# VUE_PIC32_v1_0_PIC32.net
KiCad netlist of a schematic drawn in Altium Designer
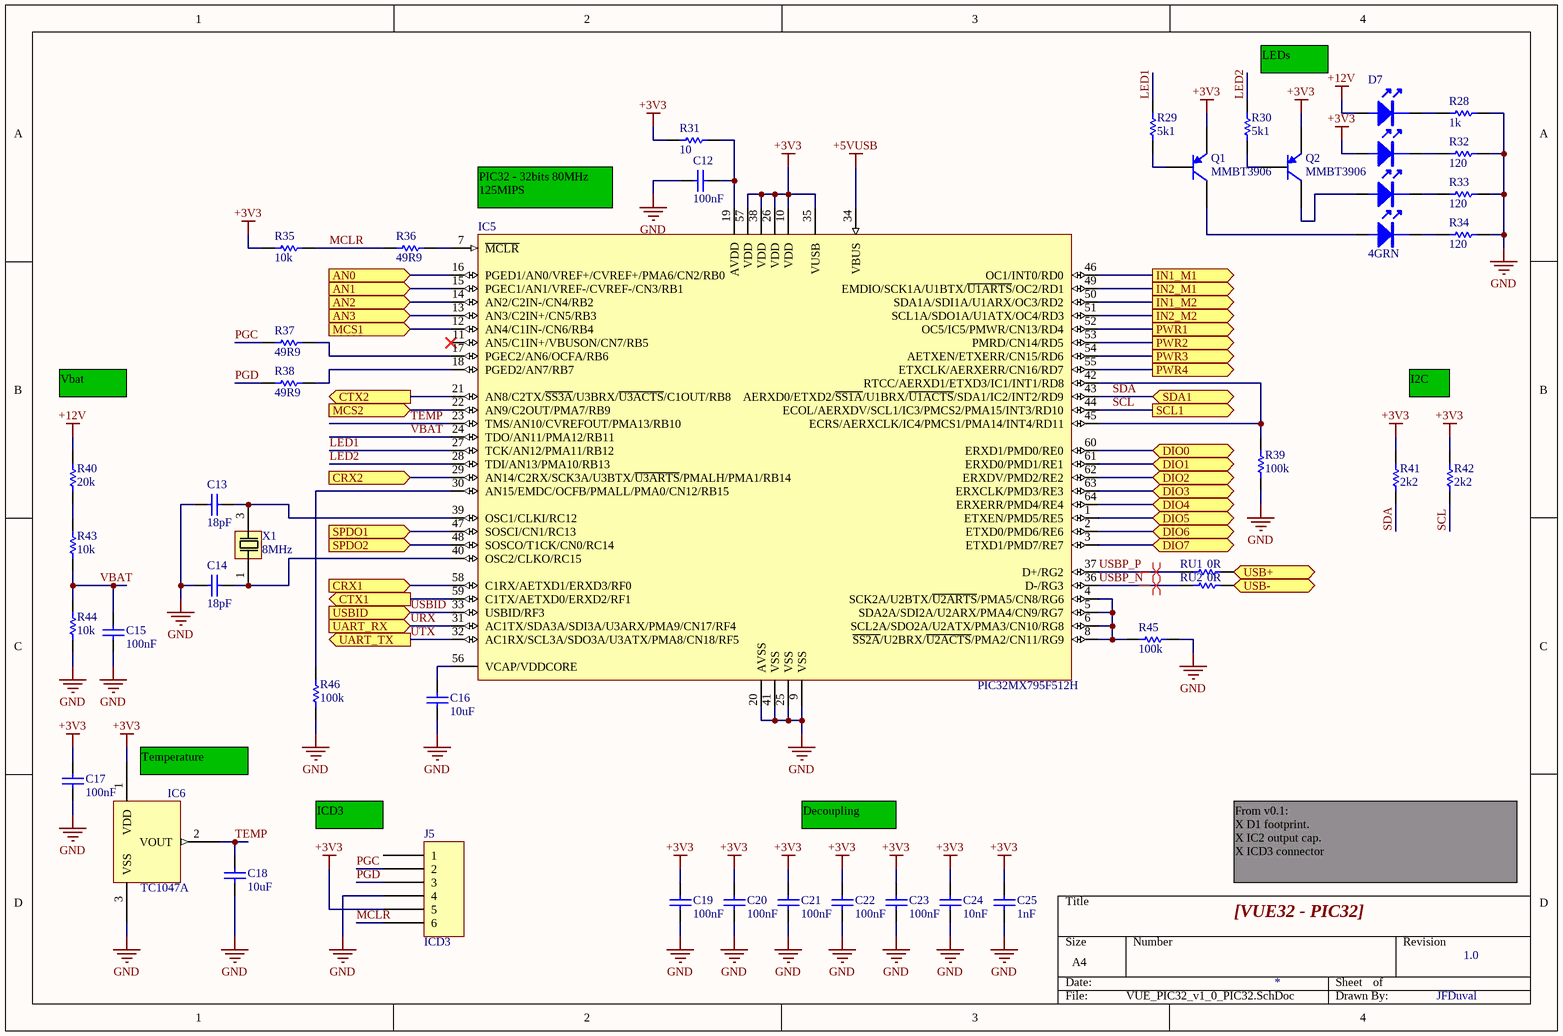
[diagram p0: VUE_PIC32_v1_0_PIC32.SchDoc]

(export (version "E")
  (design (tool "Eeschema 10.0.6"))
  (components
    (comp (ref "C12")
      (value "100nF")
      (footprint "0402C")
      (description "CAP CER 0.1UF 25V Y5V 0402")
      (fields (field (name "MFG") "TDK") (field (name "MFGPARTNUMBER") "C1005Y5V1E104Z"))
      (libsource (lib "JFD_Cap") (part "CAP_TDK_C_0402_100nF_25V"))
    )
    (comp (ref "C13")
      (value "18pF")
      (footprint "0402C")
      (description "CAP CER 18PF 50V 5% NP0 0402")
      (fields (field (name "MFG") "TDK") (field (name "MFGPARTNUMBER") "C1005C0G1H180J"))
      (libsource (lib "JFD_Cap") (part "CAP_TDK_C_0402_18pF_50V"))
    )
    (comp (ref "C14")
      (value "18pF")
      (footprint "0402C")
      (description "CAP CER 18PF 50V 5% NP0 0402")
      (fields (field (name "MFG") "TDK") (field (name "MFGPARTNUMBER") "C1005C0G1H180J"))
      (libsource (lib "JFD_Cap") (part "CAP_TDK_C_0402_18pF_50V"))
    )
    (comp (ref "C15")
      (value "100nF")
      (footprint "0402C")
      (description "CAP CER 0.1UF 25V Y5V 0402")
      (fields (field (name "MFG") "TDK") (field (name "MFGPARTNUMBER") "C1005Y5V1E104Z"))
      (libsource (lib "JFD_Cap") (part "CAP_TDK_C_0402_100nF_25V"))
    )
    (comp (ref "C16")
      (value "10uF")
      (footprint "0805C")
      (description "CAP CER 10UF 16V Y5V 0805")
      (fields (field (name "MFG") "Murata") (field (name "MFGPARTNUMBER") "GRM21BF51C106ZE15L"))
      (libsource (lib "JFD_Cap") (part "CAP_MURATA_C_0805_10uF_16V"))
    )
    (comp (ref "C17")
      (value "100nF")
      (footprint "0402C")
      (description "CAP CER 0.1UF 25V Y5V 0402")
      (fields (field (name "MFG") "TDK") (field (name "MFGPARTNUMBER") "C1005Y5V1E104Z"))
      (libsource (lib "JFD_Cap") (part "CAP_TDK_C_0402_100nF_25V"))
    )
    (comp (ref "C18")
      (value "10uF")
      (footprint "0805C")
      (description "CAP CER 10UF 16V Y5V 0805")
      (fields (field (name "MFG") "Murata") (field (name "MFGPARTNUMBER") "GRM21BF51C106ZE15L"))
      (libsource (lib "JFD_Cap") (part "CAP_MURATA_C_0805_10uF_16V"))
    )
    (comp (ref "C19")
      (value "100nF")
      (footprint "0402C")
      (description "CAP CER 0.1UF 25V Y5V 0402")
      (fields (field (name "MFG") "TDK") (field (name "MFGPARTNUMBER") "C1005Y5V1E104Z"))
      (libsource (lib "JFD_Cap") (part "CAP_TDK_C_0402_100nF_25V"))
    )
    (comp (ref "C20")
      (value "100nF")
      (footprint "0402C")
      (description "CAP CER 0.1UF 25V Y5V 0402")
      (fields (field (name "MFG") "TDK") (field (name "MFGPARTNUMBER") "C1005Y5V1E104Z"))
      (libsource (lib "JFD_Cap") (part "CAP_TDK_C_0402_100nF_25V"))
    )
    (comp (ref "C21")
      (value "100nF")
      (footprint "0402C")
      (description "CAP CER 0.1UF 25V Y5V 0402")
      (fields (field (name "MFG") "TDK") (field (name "MFGPARTNUMBER") "C1005Y5V1E104Z"))
      (libsource (lib "JFD_Cap") (part "CAP_TDK_C_0402_100nF_25V"))
    )
    (comp (ref "C22")
      (value "100nF")
      (footprint "0402C")
      (description "CAP CER 0.1UF 25V Y5V 0402")
      (fields (field (name "MFG") "TDK") (field (name "MFGPARTNUMBER") "C1005Y5V1E104Z"))
      (libsource (lib "JFD_Cap") (part "CAP_TDK_C_0402_100nF_25V"))
    )
    (comp (ref "C23")
      (value "100nF")
      (footprint "0402C")
      (description "CAP CER 0.1UF 25V Y5V 0402")
      (fields (field (name "MFG") "TDK") (field (name "MFGPARTNUMBER") "C1005Y5V1E104Z"))
      (libsource (lib "JFD_Cap") (part "CAP_TDK_C_0402_100nF_25V"))
    )
    (comp (ref "C24")
      (value "10nF")
      (footprint "0402C")
      (description "CAP CER 10000PF 25V 10% X7R 0402")
      (fields (field (name "MFG") "TDK") (field (name "MFGPARTNUMBER") "C1005X7R1E103K"))
      (libsource (lib "JFD_Cap") (part "CAP_TDK_C_0402_10nF_25V"))
    )
    (comp (ref "C25")
      (value "1nF")
      (footprint "0402C")
      (description "CAP CER 1000PF 25V 10% X7R 0402")
      (fields (field (name "MFG") "TDK") (field (name "MFGPARTNUMBER") "C1005X7R1E102K"))
      (libsource (lib "JFD_Cap") (part "CAP_TDK_C_0402_1nF_25V"))
    )
    (comp (ref "D7")
      (value "4GRN")
      (footprint "KINGBRIGHT_4HIGH_LED")
      (description "LED IND 2X3MM QUAD RA GRN DIFF")
      (fields (field (name "MFG") "Kingbright Corp") (field (name "MFGPARTNUMBER") "WP914CK/4GDT"))
      (libsource (lib "JFD_Semi") (part "LED_KINGBRIGHT_4HIGH_GREEN"))
    )
    (comp (ref "IC5")
      (value "PIC32MX795F512H")
      (footprint "TQFP-64")
      (description "IC MCU 32BIT 512KB FLASH 64TQFP")
      (fields
        (field (name "MFG") "Microchip Technology")
        (field (name "MFGPARTNUMBER") "PIC32MX795F512H-80I/PT")
      )
      (libsource (lib "JFD_IC") (part "IC_MCU_MICROCHIP_PIC32MX795F512H"))
    )
    (comp (ref "IC6")
      (value "TC1047A")
      (footprint "SOT23-3")
      (description "IC TEMP-VOLT CONV PREC SOT-23B")
      (fields (field (name "MFG") "Microchip Technology") (field (name "MFGPARTNUMBER") "TC1047AVNBTR"))
      (libsource (lib "JFD_IC") (part "IC_SENSOR_MICROCHIP_TEMP_TC1047A"))
    )
    (comp (ref "J5")
      (value "ICD3")
      (footprint "HEADER_FEMALE_DUAL_6POS_1_27MM")
      (description "CONN HEADER .050\" 6POS DL PCB AU")
      (fields
        (field (name "MFG") "Sullins Connector Solutions")
        (field (name "MFGPARTNUMBER") "LPPB032CFFN-RC")
      )
      (libsource (lib "JFD_Con") (part "CON_SULLINS_HEADER_F_3X2_6POS_1_27MM"))
    )
    (comp (ref "Q1")
      (value "MMBT3906")
      (footprint "SC-75/SOT-416")
      (description "TRANS PNP GP 40V 200MA SC75-3")
      (fields (field (name "MFG") "ON Semiconductor") (field (name "MFGPARTNUMBER") "MMBT3906TT1G"))
      (libsource (lib "JFD_Semi") (part "BJT_ONSEMI_PNP_MMBT3906_40V_200MA_SC75"))
    )
    (comp (ref "Q2")
      (value "MMBT3906")
      (footprint "SC-75/SOT-416")
      (description "TRANS PNP GP 40V 200MA SC75-3")
      (fields (field (name "MFG") "ON Semiconductor") (field (name "MFGPARTNUMBER") "MMBT3906TT1G"))
      (libsource (lib "JFD_Semi") (part "BJT_ONSEMI_PNP_MMBT3906_40V_200MA_SC75"))
    )
    (comp (ref "R28")
      (value "1k")
      (footprint "0402")
      (description "RES 1.00K OHM 1/16W 1% 0402 SMD")
      (fields (field (name "MFG") "Yageo") (field (name "MFGPARTNUMBER") "RC0402FR-071KL"))
      (libsource (lib "JFD_Res") (part "RES_YAGEO_0402_1K_1PCT"))
    )
    (comp (ref "R29")
      (value "5k1")
      (footprint "0402")
      (description "RES 5.10K OHM 1/16W 1% 0402 SMD")
      (fields (field (name "MFG") "Yageo") (field (name "MFGPARTNUMBER") "RC0402FR-075K1L"))
      (libsource (lib "JFD_Res") (part "RES_YAGEO_0402_5K1_1PCT"))
    )
    (comp (ref "R30")
      (value "5k1")
      (footprint "0402")
      (description "RES 5.10K OHM 1/16W 1% 0402 SMD")
      (fields (field (name "MFG") "Yageo") (field (name "MFGPARTNUMBER") "RC0402FR-075K1L"))
      (libsource (lib "JFD_Res") (part "RES_YAGEO_0402_5K1_1PCT"))
    )
    (comp (ref "R31")
      (value "10")
      (footprint "0402")
      (description "RES 10.0 OHM 1/16W 1% 0402 SMD")
      (fields (field (name "MFG") "Yageo") (field (name "MFGPARTNUMBER") "RC0402FR-0710RL"))
      (libsource (lib "JFD_Res") (part "RES_YAGEO_0402_10_1PCT"))
    )
    (comp (ref "R32")
      (value "120")
      (footprint "0402")
      (description "RES 120 OHM 1/16W 1% 0402 SMD")
      (fields (field (name "MFG") "Yageo") (field (name "MFGPARTNUMBER") "RC0402FR-07120RL"))
      (libsource (lib "JFD_Res") (part "RES_YAGEO_0402_120_1PCT"))
    )
    (comp (ref "R33")
      (value "120")
      (footprint "0402")
      (description "RES 120 OHM 1/16W 1% 0402 SMD")
      (fields (field (name "MFG") "Yageo") (field (name "MFGPARTNUMBER") "RC0402FR-07120RL"))
      (libsource (lib "JFD_Res") (part "RES_YAGEO_0402_120_1PCT"))
    )
    (comp (ref "R34")
      (value "120")
      (footprint "0402")
      (description "RES 120 OHM 1/16W 1% 0402 SMD")
      (fields (field (name "MFG") "Yageo") (field (name "MFGPARTNUMBER") "RC0402FR-07120RL"))
      (libsource (lib "JFD_Res") (part "RES_YAGEO_0402_120_1PCT"))
    )
    (comp (ref "R35")
      (value "10k")
      (footprint "0402")
      (description "RES 10.0K OHM 1/16W 1% 0402 SMD")
      (fields (field (name "MFG") "Yageo") (field (name "MFGPARTNUMBER") "RC0402FR-0710KL"))
      (libsource (lib "JFD_Res") (part "RES_YAGEO_0402_10K_1PCT"))
    )
    (comp (ref "R36")
      (value "49R9")
      (footprint "0402")
      (description "RES 49.9 OHM 1/16W 1% 0402 SMD")
      (fields (field (name "MFG") "Yageo") (field (name "MFGPARTNUMBER") "RC0402FR-0749R9L"))
      (libsource (lib "JFD_Res") (part "RES_YAGEO_0402_49R9_1PCT"))
    )
    (comp (ref "R37")
      (value "49R9")
      (footprint "0402")
      (description "RES 49.9 OHM 1/16W 1% 0402 SMD")
      (fields (field (name "MFG") "Yageo") (field (name "MFGPARTNUMBER") "RC0402FR-0749R9L"))
      (libsource (lib "JFD_Res") (part "RES_YAGEO_0402_49R9_1PCT"))
    )
    (comp (ref "R38")
      (value "49R9")
      (footprint "0402")
      (description "RES 49.9 OHM 1/16W 1% 0402 SMD")
      (fields (field (name "MFG") "Yageo") (field (name "MFGPARTNUMBER") "RC0402FR-0749R9L"))
      (libsource (lib "JFD_Res") (part "RES_YAGEO_0402_49R9_1PCT"))
    )
    (comp (ref "R39")
      (value "100k")
      (footprint "0402")
      (description "RES 100K OHM 1/16W 1% 0402 SMD")
      (fields (field (name "MFG") "Yageo") (field (name "MFGPARTNUMBER") "RC0402FR-07100KL"))
      (libsource (lib "JFD_Res") (part "RES_YAGEO_0402_100K_1PCT"))
    )
    (comp (ref "R40")
      (value "20k")
      (footprint "0402")
      (description "RES 20.0K OHM 1/16W 1% 0402 SMD")
      (fields (field (name "MFG") "Yageo") (field (name "MFGPARTNUMBER") "RC0402FR-0720KL"))
      (libsource (lib "JFD_Res") (part "RES_YAGEO_0402_20K_1PCT"))
    )
    (comp (ref "R41")
      (value "2k2")
      (footprint "0402")
      (description "RES 2.20K OHM 1/16W 1% 0402 SMD")
      (fields (field (name "MFG") "Yageo") (field (name "MFGPARTNUMBER") "RC0402FR-072K2L"))
      (libsource (lib "JFD_Res") (part "RES_YAGEO_0402_2K2_1PCT"))
    )
    (comp (ref "R42")
      (value "2k2")
      (footprint "0402")
      (description "RES 2.20K OHM 1/16W 1% 0402 SMD")
      (fields (field (name "MFG") "Yageo") (field (name "MFGPARTNUMBER") "RC0402FR-072K2L"))
      (libsource (lib "JFD_Res") (part "RES_YAGEO_0402_2K2_1PCT"))
    )
    (comp (ref "R43")
      (value "10k")
      (footprint "0402")
      (description "RES 10.0K OHM 1/16W 1% 0402 SMD")
      (fields (field (name "MFG") "Yageo") (field (name "MFGPARTNUMBER") "RC0402FR-0710KL"))
      (libsource (lib "JFD_Res") (part "RES_YAGEO_0402_10K_1PCT"))
    )
    (comp (ref "R44")
      (value "10k")
      (footprint "0402")
      (description "RES 10.0K OHM 1/16W 1% 0402 SMD")
      (fields (field (name "MFG") "Yageo") (field (name "MFGPARTNUMBER") "RC0402FR-0710KL"))
      (libsource (lib "JFD_Res") (part "RES_YAGEO_0402_10K_1PCT"))
    )
    (comp (ref "R45")
      (value "100k")
      (footprint "0402")
      (description "RES 100K OHM 1/16W 1% 0402 SMD")
      (fields (field (name "MFG") "Yageo") (field (name "MFGPARTNUMBER") "RC0402FR-07100KL"))
      (libsource (lib "JFD_Res") (part "RES_YAGEO_0402_100K_1PCT"))
    )
    (comp (ref "R46")
      (value "100k")
      (footprint "0402")
      (description "RES 100K OHM 1/16W 1% 0402 SMD")
      (fields (field (name "MFG") "Yageo") (field (name "MFGPARTNUMBER") "RC0402FR-07100KL"))
      (libsource (lib "JFD_Res") (part "RES_YAGEO_0402_100K_1PCT"))
    )
    (comp (ref "RU1")
      (value "0R")
      (footprint "0402")
      (description "RES 0.0 OHM 1/16W 0402 SMD")
      (fields (field (name "MFG") "Yageo") (field (name "MFGPARTNUMBER") "RC0402JR-070RL"))
      (libsource (lib "JFD_Res") (part "RES_YAGEO_0402_0R_1PCT"))
    )
    (comp (ref "RU2")
      (value "0R")
      (footprint "0402")
      (description "RES 0.0 OHM 1/16W 0402 SMD")
      (fields (field (name "MFG") "Yageo") (field (name "MFGPARTNUMBER") "RC0402JR-070RL"))
      (libsource (lib "JFD_Res") (part "RES_YAGEO_0402_0R_1PCT"))
    )
    (comp (ref "X1")
      (value "8MHz")
      (footprint "ABBM2")
      (description "CRYSTAL 8.000 MHZ 18PF SMD")
      (fields (field (name "MFG") "Abracon Corporation") (field (name "MFGPARTNUMBER") "ABMM2-8.000MHZ-E2-T"))
      (libsource (lib "JFD_Misc") (part "CRYSTAL_ABRACON_8MHZ_OSC"))
    )
  )
  (nets
    (net (code "1") (name "+3V3") (class "Default")
      (node (ref "C17") (pin "1") (pinfunction "1_1") (pintype "passive"))
      (node (ref "C19") (pin "1") (pinfunction "1_1") (pintype "passive"))
      (node (ref "C20") (pin "1") (pinfunction "1_1") (pintype "passive"))
      (node (ref "C21") (pin "1") (pinfunction "1_1") (pintype "passive"))
      (node (ref "C22") (pin "1") (pinfunction "1_1") (pintype "passive"))
      (node (ref "C23") (pin "1") (pinfunction "1_1") (pintype "passive"))
      (node (ref "C24") (pin "2") (pinfunction "2_2") (pintype "passive"))
      (node (ref "C25") (pin "2") (pinfunction "2_2") (pintype "passive"))
      (node (ref "D7") (pin "A3") (pinfunction "A3_A3") (pintype "passive"))
      (node (ref "IC5") (pin "10") (pinfunction "VDD_10") (pintype "power_in"))
      (node (ref "IC5") (pin "26") (pinfunction "VDD_26") (pintype "power_in"))
      (node (ref "IC5") (pin "35") (pinfunction "VUSB_35") (pintype "power_in"))
      (node (ref "IC5") (pin "38") (pinfunction "VDD_38") (pintype "power_in"))
      (node (ref "IC5") (pin "57") (pinfunction "VDD_57") (pintype "power_in"))
      (node (ref "IC6") (pin "1") (pinfunction "VDD_1") (pintype "power_in"))
      (node (ref "J5") (pin "5") (pinfunction "5_5") (pintype "passive"))
      (node (ref "Q1") (pin "2") (pinfunction "E_2") (pintype "passive"))
      (node (ref "Q2") (pin "2") (pinfunction "E_2") (pintype "passive"))
      (node (ref "R31") (pin "2") (pinfunction "2_2") (pintype "passive"))
      (node (ref "R35") (pin "1") (pinfunction "1_1") (pintype "passive"))
      (node (ref "R41") (pin "2") (pinfunction "2_2") (pintype "passive"))
      (node (ref "R42") (pin "2") (pinfunction "2_2") (pintype "passive"))
    )
    (net (code "2") (name "+5VUSB") (class "Default")
      (node (ref "IC5") (pin "34") (pinfunction "VBUS_34") (pintype "input"))
    )
    (net (code "3") (name "+12V") (class "Default")
      (node (ref "D7") (pin "A4") (pinfunction "A4_A4") (pintype "passive"))
      (node (ref "R40") (pin "2") (pinfunction "2_2") (pintype "passive"))
    )
    (net (code "4") (name "/AN0") (class "Default")
      (node (ref "IC5") (pin "16") (pinfunction "PGED1/AN0/VREF+/CVREF+/PMA6/CN2/RB0_16") (pintype "bidirectional"))
    )
    (net (code "5") (name "/AN1") (class "Default")
      (node (ref "IC5") (pin "15") (pinfunction "PGEC1/AN1/VREF-/CVREF-/CN3/RB1_15") (pintype "bidirectional"))
    )
    (net (code "6") (name "/AN2") (class "Default")
      (node (ref "IC5") (pin "14") (pinfunction "AN2/C2IN-/CN4/RB2_14") (pintype "bidirectional"))
    )
    (net (code "7") (name "/AN3") (class "Default")
      (node (ref "IC5") (pin "13") (pinfunction "AN3/C2IN+/CN5/RB3_13") (pintype "bidirectional"))
    )
    (net (code "8") (name "/CRX1") (class "Default")
      (node (ref "IC5") (pin "58") (pinfunction "C1RX/AETXD1/ERXD3/RF0_58") (pintype "bidirectional"))
    )
    (net (code "9") (name "/CRX2") (class "Default")
      (node (ref "IC5") (pin "29") (pinfunction "AN14/C2RX/SCK3A/U3BTX/~{U3ARTS}/PMALH/PMA1/RB14_29") (pintype "bidirectional"))
    )
    (net (code "10") (name "/CTX1") (class "Default")
      (node (ref "IC5") (pin "59") (pinfunction "C1TX/AETXD0/ERXD2/RF1_59") (pintype "bidirectional"))
    )
    (net (code "11") (name "/CTX2") (class "Default")
      (node (ref "IC5") (pin "21") (pinfunction "AN8/C2TX/~{SS3A}/U3BRX/~{U3ACTS}/C1OUT/RB8_21") (pintype "bidirectional"))
    )
    (net (code "12") (name "/DIO0") (class "Default")
      (node (ref "IC5") (pin "60") (pinfunction "ERXD1/PMD0/RE0_60") (pintype "bidirectional"))
    )
    (net (code "13") (name "/DIO1") (class "Default")
      (node (ref "IC5") (pin "61") (pinfunction "ERXD0/PMD1/RE1_61") (pintype "bidirectional"))
    )
    (net (code "14") (name "/DIO2") (class "Default")
      (node (ref "IC5") (pin "62") (pinfunction "ERXDV/PMD2/RE2_62") (pintype "bidirectional"))
    )
    (net (code "15") (name "/DIO3") (class "Default")
      (node (ref "IC5") (pin "63") (pinfunction "ERXCLK/PMD3/RE3_63") (pintype "bidirectional"))
    )
    (net (code "16") (name "/DIO4") (class "Default")
      (node (ref "IC5") (pin "64") (pinfunction "ERXERR/PMD4/RE4_64") (pintype "bidirectional"))
    )
    (net (code "17") (name "/DIO5") (class "Default")
      (node (ref "IC5") (pin "1") (pinfunction "ETXEN/PMD5/RE5_1") (pintype "bidirectional"))
    )
    (net (code "18") (name "/DIO6") (class "Default")
      (node (ref "IC5") (pin "2") (pinfunction "ETXD0/PMD6/RE6_2") (pintype "bidirectional"))
    )
    (net (code "19") (name "/DIO7") (class "Default")
      (node (ref "IC5") (pin "3") (pinfunction "ETXD1/PMD7/RE7_3") (pintype "bidirectional"))
    )
    (net (code "20") (name "/IN1_M1") (class "Default")
      (node (ref "IC5") (pin "46") (pinfunction "OC1/INT0/RD0_46") (pintype "bidirectional"))
    )
    (net (code "21") (name "/IN1_M2") (class "Default")
      (node (ref "IC5") (pin "50") (pinfunction "SDA1A/SDI1A/U1ARX/OC3/RD2_50") (pintype "bidirectional"))
    )
    (net (code "22") (name "/IN2_M1") (class "Default")
      (node (ref "IC5") (pin "49") (pinfunction "EMDIO/SCK1A/U1BTX/~{U1ARTS}/OC2/RD1_49") (pintype "bidirectional"))
    )
    (net (code "23") (name "/IN2_M2") (class "Default")
      (node (ref "IC5") (pin "51") (pinfunction "SCL1A/SDO1A/U1ATX/OC4/RD3_51") (pintype "bidirectional"))
    )
    (net (code "24") (name "/LED1") (class "Default")
      (node (ref "IC5") (pin "27") (pinfunction "TCK/AN12/PMA11/RB12_27") (pintype "bidirectional"))
      (node (ref "R29") (pin "2") (pinfunction "2_2") (pintype "passive"))
    )
    (net (code "25") (name "/LED2") (class "Default")
      (node (ref "IC5") (pin "28") (pinfunction "TDI/AN13/PMA10/RB13_28") (pintype "bidirectional"))
      (node (ref "R30") (pin "2") (pinfunction "2_2") (pintype "passive"))
    )
    (net (code "26") (name "/MCLR") (class "Default")
      (node (ref "J5") (pin "6") (pinfunction "6_6") (pintype "passive"))
      (node (ref "R35") (pin "2") (pinfunction "2_2") (pintype "passive"))
      (node (ref "R36") (pin "1") (pinfunction "1_1") (pintype "passive"))
    )
    (net (code "27") (name "/MCS1") (class "Default")
      (node (ref "IC5") (pin "12") (pinfunction "AN4/C1IN-/CN6/RB4_12") (pintype "bidirectional"))
    )
    (net (code "28") (name "/MCS2") (class "Default")
      (node (ref "IC5") (pin "22") (pinfunction "AN9/C2OUT/PMA7/RB9_22") (pintype "bidirectional"))
    )
    (net (code "29") (name "/PGC") (class "Default")
      (node (ref "J5") (pin "2") (pinfunction "2_2") (pintype "passive"))
      (node (ref "R37") (pin "1") (pinfunction "1_1") (pintype "passive"))
    )
    (net (code "30") (name "/PGD") (class "Default")
      (node (ref "J5") (pin "3") (pinfunction "3_3") (pintype "passive"))
      (node (ref "R38") (pin "1") (pinfunction "1_1") (pintype "passive"))
    )
    (net (code "31") (name "/PWR1") (class "Default")
      (node (ref "IC5") (pin "52") (pinfunction "OC5/IC5/PMWR/CN13/RD4_52") (pintype "bidirectional"))
    )
    (net (code "32") (name "/PWR2") (class "Default")
      (node (ref "IC5") (pin "53") (pinfunction "PMRD/CN14/RD5_53") (pintype "bidirectional"))
    )
    (net (code "33") (name "/PWR3") (class "Default")
      (node (ref "IC5") (pin "54") (pinfunction "AETXEN/ETXERR/CN15/RD6_54") (pintype "bidirectional"))
    )
    (net (code "34") (name "/PWR4") (class "Default")
      (node (ref "IC5") (pin "55") (pinfunction "ETXCLK/AERXERR/CN16/RD7_55") (pintype "bidirectional"))
    )
    (net (code "35") (name "/SCL") (class "Default")
      (node (ref "IC5") (pin "44") (pinfunction "ECOL/AERXDV/SCL1/IC3/PMCS2/PMA15/INT3/RD10_44") (pintype "bidirectional"))
      (node (ref "R42") (pin "1") (pinfunction "1_1") (pintype "passive"))
    )
    (net (code "36") (name "/SDA") (class "Default")
      (node (ref "IC5") (pin "43") (pinfunction "AERXD0/ETXD2/~{SS1A}/U1BRX/~{U1ACTS}/SDA1/IC2/INT2/RD9_43") (pintype "bidirectional"))
      (node (ref "R41") (pin "1") (pinfunction "1_1") (pintype "passive"))
    )
    (net (code "37") (name "/SPDO1") (class "Default")
      (node (ref "IC5") (pin "47") (pinfunction "SOSCI/CN1/RC13_47") (pintype "bidirectional"))
    )
    (net (code "38") (name "/SPDO2") (class "Default")
      (node (ref "IC5") (pin "48") (pinfunction "SOSCO/T1CK/CN0/RC14_48") (pintype "bidirectional"))
    )
    (net (code "39") (name "/TEMP") (class "Default")
      (node (ref "C18") (pin "2") (pinfunction "2_2") (pintype "passive"))
      (node (ref "IC5") (pin "23") (pinfunction "TMS/AN10/CVREFOUT/PMA13/RB10_23") (pintype "bidirectional"))
      (node (ref "IC6") (pin "2") (pinfunction "VOUT_2") (pintype "output"))
    )
    (net (code "40") (name "/URX") (class "Default")
      (node (ref "IC5") (pin "31") (pinfunction "AC1TX/SDA3A/SDI3A/U3ARX/PMA9/CN17/RF4_31") (pintype "bidirectional"))
    )
    (net (code "41") (name "/USB+") (class "Default")
      (node (ref "RU1") (pin "2") (pinfunction "2_2") (pintype "passive"))
    )
    (net (code "42") (name "/USB-") (class "Default")
      (node (ref "RU2") (pin "2") (pinfunction "2_2") (pintype "passive"))
    )
    (net (code "43") (name "/USBID") (class "Default")
      (node (ref "IC5") (pin "33") (pinfunction "USBID/RF3_33") (pintype "bidirectional"))
    )
    (net (code "44") (name "/USBP_N") (class "Default")
      (node (ref "IC5") (pin "36") (pinfunction "D-/RG3_36") (pintype "bidirectional"))
      (node (ref "RU2") (pin "1") (pinfunction "1_1") (pintype "passive"))
    )
    (net (code "45") (name "/USBP_P") (class "Default")
      (node (ref "IC5") (pin "37") (pinfunction "D+/RG2_37") (pintype "bidirectional"))
      (node (ref "RU1") (pin "1") (pinfunction "1_1") (pintype "passive"))
    )
    (net (code "46") (name "/UTX") (class "Default")
      (node (ref "IC5") (pin "32") (pinfunction "AC1RX/SCL3A/SDO3A/U3ATX/PMA8/CN18/RF5_32") (pintype "bidirectional"))
    )
    (net (code "47") (name "/VBAT") (class "Default")
      (node (ref "C15") (pin "1") (pinfunction "1_1") (pintype "passive"))
      (node (ref "IC5") (pin "24") (pinfunction "TDO/AN11/PMA12/RB11_24") (pintype "bidirectional"))
      (node (ref "R43") (pin "1") (pinfunction "1_1") (pintype "passive"))
      (node (ref "R44") (pin "2") (pinfunction "2_2") (pintype "passive"))
    )
    (net (code "48") (name "GND") (class "Default")
      (node (ref "C12") (pin "2") (pinfunction "2_2") (pintype "passive"))
      (node (ref "C13") (pin "2") (pinfunction "2_2") (pintype "passive"))
      (node (ref "C14") (pin "2") (pinfunction "2_2") (pintype "passive"))
      (node (ref "C15") (pin "2") (pinfunction "2_2") (pintype "passive"))
      (node (ref "C16") (pin "1") (pinfunction "1_1") (pintype "passive"))
      (node (ref "C17") (pin "2") (pinfunction "2_2") (pintype "passive"))
      (node (ref "C18") (pin "1") (pinfunction "1_1") (pintype "passive"))
      (node (ref "C19") (pin "2") (pinfunction "2_2") (pintype "passive"))
      (node (ref "C20") (pin "2") (pinfunction "2_2") (pintype "passive"))
      (node (ref "C21") (pin "2") (pinfunction "2_2") (pintype "passive"))
      (node (ref "C22") (pin "2") (pinfunction "2_2") (pintype "passive"))
      (node (ref "C23") (pin "2") (pinfunction "2_2") (pintype "passive"))
      (node (ref "C24") (pin "1") (pinfunction "1_1") (pintype "passive"))
      (node (ref "C25") (pin "1") (pinfunction "1_1") (pintype "passive"))
      (node (ref "IC5") (pin "20") (pinfunction "AVSS_20") (pintype "power_in"))
      (node (ref "IC5") (pin "25") (pinfunction "VSS_25") (pintype "power_in"))
      (node (ref "IC5") (pin "41") (pinfunction "VSS_41") (pintype "power_in"))
      (node (ref "IC5") (pin "9") (pinfunction "VSS_9") (pintype "power_in"))
      (node (ref "IC6") (pin "3") (pinfunction "VSS_3") (pintype "power_in"))
      (node (ref "J5") (pin "4") (pinfunction "4_4") (pintype "passive"))
      (node (ref "R28") (pin "1") (pinfunction "1_1") (pintype "passive"))
      (node (ref "R32") (pin "2") (pinfunction "2_2") (pintype "passive"))
      (node (ref "R33") (pin "2") (pinfunction "2_2") (pintype "passive"))
      (node (ref "R34") (pin "2") (pinfunction "2_2") (pintype "passive"))
      (node (ref "R39") (pin "1") (pinfunction "1_1") (pintype "passive"))
      (node (ref "R44") (pin "1") (pinfunction "1_1") (pintype "passive"))
      (node (ref "R45") (pin "2") (pinfunction "2_2") (pintype "passive"))
      (node (ref "R46") (pin "1") (pinfunction "1_1") (pintype "passive"))
    )
    (net (code "49") (name "Net-(D7-PadC1)") (class "Default")
      (node (ref "D7") (pin "C1") (pinfunction "C1_C1") (pintype "passive"))
      (node (ref "R34") (pin "1") (pinfunction "1_1") (pintype "passive"))
    )
    (net (code "50") (name "Net-(D7-PadC2)") (class "Default")
      (node (ref "D7") (pin "C2") (pinfunction "C2_C2") (pintype "passive"))
      (node (ref "R33") (pin "1") (pinfunction "1_1") (pintype "passive"))
    )
    (net (code "51") (name "Net-(D7-PadC3)") (class "Default")
      (node (ref "D7") (pin "C3") (pinfunction "C3_C3") (pintype "passive"))
      (node (ref "R32") (pin "1") (pinfunction "1_1") (pintype "passive"))
    )
    (net (code "52") (name "Net-(D7-PadC4)") (class "Default")
      (node (ref "D7") (pin "C4") (pinfunction "C4_C4") (pintype "passive"))
      (node (ref "R28") (pin "2") (pinfunction "2_2") (pintype "passive"))
    )
    (net (code "53") (name "Net-(IC5-AN15{slash}EMDC{slash}OCFB{slash}PMALL{slash}PMA0{slash}CN12{slash}RB15)") (class "Default")
      (node (ref "IC5") (pin "30") (pinfunction "AN15/EMDC/OCFB/PMALL/PMA0/CN12/RB15_30") (pintype "bidirectional"))
      (node (ref "R46") (pin "2") (pinfunction "2_2") (pintype "passive"))
    )
    (net (code "54") (name "Net-(IC5-AVDD)") (class "Default")
      (node (ref "C12") (pin "1") (pinfunction "1_1") (pintype "passive"))
      (node (ref "IC5") (pin "19") (pinfunction "AVDD_19") (pintype "power_in"))
      (node (ref "R31") (pin "1") (pinfunction "1_1") (pintype "passive"))
    )
    (net (code "55") (name "Net-(IC5-ECRS{slash}AERXCLK{slash}IC4{slash}PMCS1{slash}PMA14{slash}INT4{slash}RD11)") (class "Default")
      (node (ref "IC5") (pin "42") (pinfunction "RTCC/AERXD1/ETXD3/IC1/INT1/RD8_42") (pintype "bidirectional"))
      (node (ref "IC5") (pin "45") (pinfunction "ECRS/AERXCLK/IC4/PMCS1/PMA14/INT4/RD11_45") (pintype "bidirectional"))
      (node (ref "R39") (pin "2") (pinfunction "2_2") (pintype "passive"))
    )
    (net (code "56") (name "Net-(IC5-OSC1{slash}CLKI{slash}RC12)") (class "Default")
      (node (ref "C13") (pin "1") (pinfunction "1_1") (pintype "passive"))
      (node (ref "IC5") (pin "39") (pinfunction "OSC1/CLKI/RC12_39") (pintype "bidirectional"))
      (node (ref "X1") (pin "3") (pinfunction "B_3") (pintype "passive"))
    )
    (net (code "57") (name "Net-(IC5-OSC2{slash}CLKO{slash}RC15)") (class "Default")
      (node (ref "C14") (pin "1") (pinfunction "1_1") (pintype "passive"))
      (node (ref "IC5") (pin "40") (pinfunction "OSC2/CLKO/RC15_40") (pintype "bidirectional"))
      (node (ref "X1") (pin "1") (pinfunction "A_1") (pintype "passive"))
    )
    (net (code "58") (name "Net-(IC5-PGEC2{slash}AN6{slash}OCFA{slash}RB6)") (class "Default")
      (node (ref "IC5") (pin "17") (pinfunction "PGEC2/AN6/OCFA/RB6_17") (pintype "bidirectional"))
      (node (ref "R37") (pin "2") (pinfunction "2_2") (pintype "passive"))
    )
    (net (code "59") (name "Net-(IC5-PGED2{slash}AN7{slash}RB7)") (class "Default")
      (node (ref "IC5") (pin "18") (pinfunction "PGED2/AN7/RB7_18") (pintype "bidirectional"))
      (node (ref "R38") (pin "2") (pinfunction "2_2") (pintype "passive"))
    )
    (net (code "60") (name "Net-(IC5-SCK2A{slash}U2BTX{slash}~{U2ARTS}{slash}PMA5{slash}CN8{slash}RG6)") (class "Default")
      (node (ref "IC5") (pin "4") (pinfunction "SCK2A/U2BTX/~{U2ARTS}/PMA5/CN8/RG6_4") (pintype "bidirectional"))
      (node (ref "IC5") (pin "5") (pinfunction "SDA2A/SDI2A/U2ARX/PMA4/CN9/RG7_5") (pintype "bidirectional"))
      (node (ref "IC5") (pin "6") (pinfunction "SCL2A/SDO2A/U2ATX/PMA3/CN10/RG8_6") (pintype "bidirectional"))
      (node (ref "IC5") (pin "8") (pinfunction "~{SS2A}/U2BRX/~{U2ACTS}/PMA2/CN11/RG9_8") (pintype "bidirectional"))
      (node (ref "R45") (pin "1") (pinfunction "1_1") (pintype "passive"))
    )
    (net (code "61") (name "Net-(IC5-VCAP{slash}VDDCORE)") (class "Default")
      (node (ref "C16") (pin "2") (pinfunction "2_2") (pintype "passive"))
      (node (ref "IC5") (pin "56") (pinfunction "VCAP/VDDCORE_56") (pintype "power_in"))
    )
    (net (code "62") (name "Net-(IC5-~{MCLR})") (class "Default")
      (node (ref "IC5") (pin "7") (pinfunction "~{MCLR}_7") (pintype "input"))
      (node (ref "R36") (pin "2") (pinfunction "2_2") (pintype "passive"))
    )
    (net (code "63") (name "Net-(Q1-B)") (class "Default")
      (node (ref "Q1") (pin "1") (pinfunction "B_1") (pintype "passive"))
      (node (ref "R29") (pin "1") (pinfunction "1_1") (pintype "passive"))
    )
    (net (code "64") (name "Net-(Q1-C)") (class "Default")
      (node (ref "D7") (pin "A1") (pinfunction "A1_A1") (pintype "passive"))
      (node (ref "Q1") (pin "3") (pinfunction "C_3") (pintype "passive"))
    )
    (net (code "65") (name "Net-(Q2-B)") (class "Default")
      (node (ref "Q2") (pin "1") (pinfunction "B_1") (pintype "passive"))
      (node (ref "R30") (pin "1") (pinfunction "1_1") (pintype "passive"))
    )
    (net (code "66") (name "Net-(Q2-C)") (class "Default")
      (node (ref "D7") (pin "A2") (pinfunction "A2_A2") (pintype "passive"))
      (node (ref "Q2") (pin "3") (pinfunction "C_3") (pintype "passive"))
    )
    (net (code "67") (name "Net-(R40-Pad1)") (class "Default")
      (node (ref "R40") (pin "1") (pinfunction "1_1") (pintype "passive"))
      (node (ref "R43") (pin "2") (pinfunction "2_2") (pintype "passive"))
    )
    (net (code "68") (name "unconnected-(IC5-AN5{slash}C1IN+{slash}VBUSON{slash}CN7{slash}RB5-Pad11)") (class "Default")
      (node (ref "IC5") (pin "11") (pinfunction "AN5/C1IN+/VBUSON/CN7/RB5_11") (pintype "bidirectional+no_connect"))
    )
    (net (code "69") (name "unconnected-(J5-Pad1)") (class "Default")
      (node (ref "J5") (pin "1") (pinfunction "1_1") (pintype "passive"))
    )
  )
)
